# Sheet1.net
KiCad netlist of a schematic drawn in Altium Designer
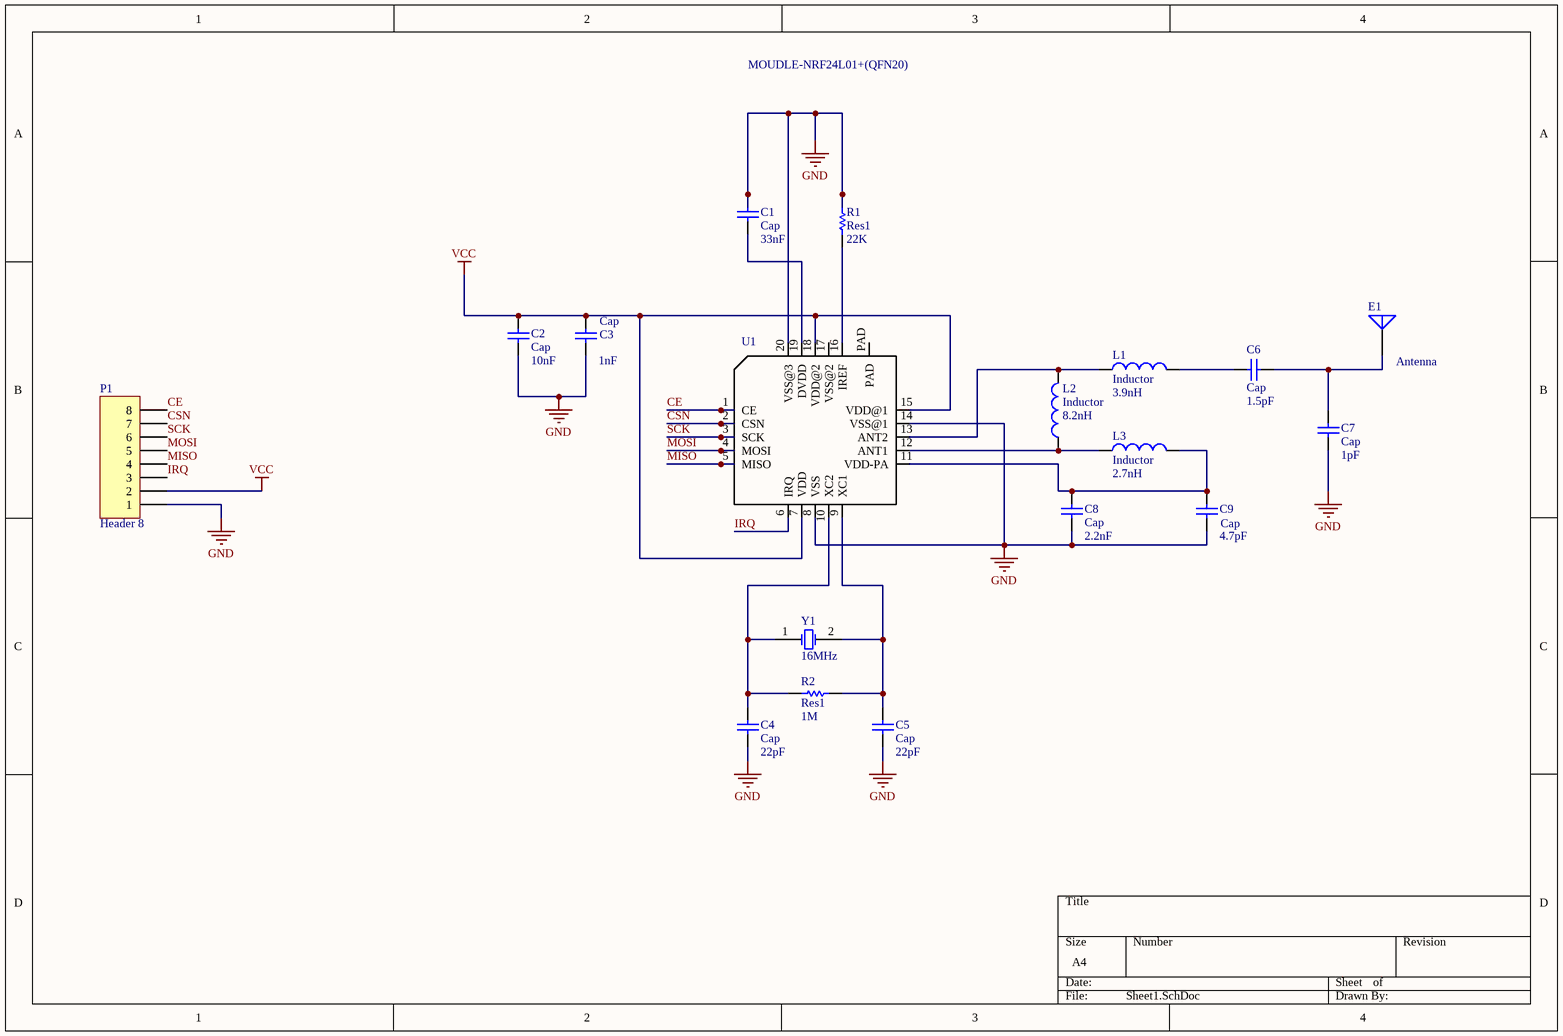
[diagram p0: Sheet1.SchDoc]

(export (version "E")
  (design (tool "Eeschema 10.0.6"))
  (components
    (comp (ref "C1")
      (value "Cap")
      (footprint "6-0805_L")
      (description "Capacitor")
      (fields (field (name "ALTIUM_VALUE") "33nF") (field (name "PUBLISHER") "Altium Limited"))
      (libsource (lib "Miscellaneous Devices") (part "Cap"))
    )
    (comp (ref "C2")
      (value "Cap")
      (footprint "6-0805_L")
      (description "Capacitor")
      (fields (field (name "ALTIUM_VALUE") "10nF") (field (name "PUBLISHER") "Altium Limited"))
      (libsource (lib "Miscellaneous Devices") (part "Cap"))
    )
    (comp (ref "C3")
      (value "Cap")
      (footprint "6-0805_L")
      (description "Capacitor")
      (fields (field (name "ALTIUM_VALUE") "1nF") (field (name "PUBLISHER") "Altium Limited"))
      (libsource (lib "Miscellaneous Devices") (part "Cap"))
    )
    (comp (ref "C4")
      (value "Cap")
      (footprint "6-0805_L")
      (description "Capacitor")
      (fields (field (name "ALTIUM_VALUE") "22pF") (field (name "PUBLISHER") "Altium Limited"))
      (libsource (lib "Miscellaneous Devices") (part "Cap"))
    )
    (comp (ref "C5")
      (value "Cap")
      (footprint "6-0805_L")
      (description "Capacitor")
      (fields (field (name "ALTIUM_VALUE") "22pF") (field (name "PUBLISHER") "Altium Limited"))
      (libsource (lib "Miscellaneous Devices") (part "Cap"))
    )
    (comp (ref "C6")
      (value "Cap")
      (footprint "6-0805_L")
      (description "Capacitor")
      (fields (field (name "ALTIUM_VALUE") "1.5pF") (field (name "PUBLISHER") "Altium Limited"))
      (libsource (lib "Miscellaneous Devices") (part "Cap"))
    )
    (comp (ref "C7")
      (value "Cap")
      (footprint "6-0805_L")
      (description "Capacitor")
      (fields (field (name "ALTIUM_VALUE") "1pF") (field (name "PUBLISHER") "Altium Limited"))
      (libsource (lib "Miscellaneous Devices") (part "Cap"))
    )
    (comp (ref "C8")
      (value "Cap")
      (footprint "6-0805_L")
      (description "Capacitor")
      (fields (field (name "ALTIUM_VALUE") "2.2nF") (field (name "PUBLISHER") "Altium Limited"))
      (libsource (lib "Miscellaneous Devices") (part "Cap"))
    )
    (comp (ref "C9")
      (value "Cap")
      (footprint "6-0805_L")
      (description "Capacitor")
      (fields (field (name "ALTIUM_VALUE") "4.7pF") (field (name "PUBLISHER") "Altium Limited"))
      (libsource (lib "Miscellaneous Devices") (part "Cap"))
    )
    (comp (ref "E1")
      (value "Antenna")
      (footprint "ANT_SMA_RP_FEMEA_90G")
      (description "Generic Antenna")
      (fields (field (name "PUBLISHER") "Altium Limited"))
      (libsource (lib "Miscellaneous Devices") (part "Antenna"))
    )
    (comp (ref "L1")
      (value "Inductor")
      (footprint "0805IND")
      (fields (field (name "ALTIUM_VALUE") "3.9nH") (field (name "PUBLISHER") "Altium Limited"))
      (libsource (lib "Miscellaneous Devices") (part "Inductor"))
    )
    (comp (ref "L2")
      (value "Inductor")
      (footprint "0805IND")
      (fields (field (name "ALTIUM_VALUE") "8.2nH") (field (name "PUBLISHER") "Altium Limited"))
      (libsource (lib "Miscellaneous Devices") (part "Inductor"))
    )
    (comp (ref "L3")
      (value "Inductor")
      (footprint "0805IND")
      (fields (field (name "ALTIUM_VALUE") "2.7nH") (field (name "PUBLISHER") "Altium Limited"))
      (libsource (lib "Miscellaneous Devices") (part "Inductor"))
    )
    (comp (ref "P1")
      (value "Header 8")
      (footprint "HDR2X4")
      (description "Header, 8-Pin")
      (fields (field (name "PUBLISHER") "Altium Limited"))
      (libsource (lib "Miscellaneous Connectors") (part "Header 8"))
    )
    (comp (ref "R1")
      (value "Res1")
      (footprint "6-0805_L")
      (description "Resistor")
      (fields (field (name "ALTIUM_VALUE") "22K") (field (name "PUBLISHER") "Altium Limited"))
      (libsource (lib "Miscellaneous Devices") (part "Res1"))
    )
    (comp (ref "R2")
      (value "Res1")
      (footprint "6-0805_L")
      (description "Resistor")
      (fields (field (name "ALTIUM_VALUE") "1M") (field (name "PUBLISHER") "Altium Limited"))
      (libsource (lib "Miscellaneous Devices") (part "Res1"))
    )
    (comp (ref "U1")
      (value "MOUDLE-NRF24L01+(QFN20)")
      (footprint "*QFN20G-0.5-4X4MM_MOUDLE-NRF24L01+(QFN20)(Primary)")
      (fields (field (name "MP") "NRF24L01+MODULE") (field (name "MF") "Seeed Technology"))
      (libsource (lib "MOUDLE-NRF24L01__QFN20_") (part "MOUDLE-NRF24L01+(QFN20)"))
    )
    (comp (ref "Y1")
      (value "16MHz")
      (footprint "R38")
      (description "Crystal Oscillator")
      (fields (field (name "PUBLISHER") "Altium Limited"))
      (libsource (lib "Miscellaneous Devices") (part "XTAL"))
    )
  )
  (nets
    (net (code "1") (name "/CE") (class "Default")
      (node (ref "P1") (pin "8") (pinfunction "8_8") (pintype "passive"))
      (node (ref "U1") (pin "1") (pinfunction "CE_1") (pintype "bidirectional"))
    )
    (net (code "2") (name "/CSN") (class "Default")
      (node (ref "P1") (pin "7") (pinfunction "7_7") (pintype "passive"))
      (node (ref "U1") (pin "2") (pinfunction "CSN_2") (pintype "bidirectional"))
    )
    (net (code "3") (name "/IRQ") (class "Default")
      (node (ref "P1") (pin "3") (pinfunction "3_3") (pintype "passive"))
      (node (ref "U1") (pin "6") (pinfunction "IRQ_6") (pintype "bidirectional"))
    )
    (net (code "4") (name "/MISO") (class "Default")
      (node (ref "P1") (pin "4") (pinfunction "4_4") (pintype "passive"))
      (node (ref "U1") (pin "5") (pinfunction "MISO_5") (pintype "bidirectional"))
    )
    (net (code "5") (name "/MOSI") (class "Default")
      (node (ref "P1") (pin "5") (pinfunction "5_5") (pintype "passive"))
      (node (ref "U1") (pin "4") (pinfunction "MOSI_4") (pintype "bidirectional"))
    )
    (net (code "6") (name "/SCK") (class "Default")
      (node (ref "P1") (pin "6") (pinfunction "6_6") (pintype "passive"))
      (node (ref "U1") (pin "3") (pinfunction "SCK_3") (pintype "bidirectional"))
    )
    (net (code "7") (name "GND") (class "Default")
      (node (ref "C1") (pin "2") (pinfunction "2_2") (pintype "passive"))
      (node (ref "C2") (pin "1") (pinfunction "1_1") (pintype "passive"))
      (node (ref "C3") (pin "1") (pinfunction "1_1") (pintype "passive"))
      (node (ref "C4") (pin "1") (pinfunction "1_1") (pintype "passive"))
      (node (ref "C5") (pin "1") (pinfunction "1_1") (pintype "passive"))
      (node (ref "C7") (pin "1") (pinfunction "1_1") (pintype "passive"))
      (node (ref "C8") (pin "1") (pinfunction "1_1") (pintype "passive"))
      (node (ref "C9") (pin "1") (pinfunction "1_1") (pintype "passive"))
      (node (ref "P1") (pin "1") (pinfunction "1_1") (pintype "passive"))
      (node (ref "R1") (pin "2") (pinfunction "2_2") (pintype "passive"))
      (node (ref "U1") (pin "14") (pinfunction "VSS@1_14") (pintype "bidirectional"))
      (node (ref "U1") (pin "20") (pinfunction "VSS@3_20") (pintype "bidirectional"))
      (node (ref "U1") (pin "8") (pinfunction "VSS_8") (pintype "bidirectional"))
    )
    (net (code "8") (name "Net-(C6-Pad1)") (class "Default")
      (node (ref "C6") (pin "1") (pinfunction "1_1") (pintype "passive"))
      (node (ref "L1") (pin "2") (pinfunction "2_2") (pintype "passive"))
    )
    (net (code "9") (name "Net-(E1-A)") (class "Default")
      (node (ref "C6") (pin "2") (pinfunction "2_2") (pintype "passive"))
      (node (ref "C7") (pin "2") (pinfunction "2_2") (pintype "passive"))
      (node (ref "E1") (pin "1") (pinfunction "A_1") (pintype "passive"))
    )
    (net (code "10") (name "Net-(U1-ANT1)") (class "Default")
      (node (ref "L2") (pin "1") (pinfunction "1_1") (pintype "passive"))
      (node (ref "L3") (pin "1") (pinfunction "1_1") (pintype "passive"))
      (node (ref "U1") (pin "12") (pinfunction "ANT1_12") (pintype "bidirectional"))
    )
    (net (code "11") (name "Net-(U1-ANT2)") (class "Default")
      (node (ref "L1") (pin "1") (pinfunction "1_1") (pintype "passive"))
      (node (ref "L2") (pin "2") (pinfunction "2_2") (pintype "passive"))
      (node (ref "U1") (pin "13") (pinfunction "ANT2_13") (pintype "bidirectional"))
    )
    (net (code "12") (name "Net-(U1-DVDD)") (class "Default")
      (node (ref "C1") (pin "1") (pinfunction "1_1") (pintype "passive"))
      (node (ref "U1") (pin "19") (pinfunction "DVDD_19") (pintype "bidirectional"))
    )
    (net (code "13") (name "Net-(U1-IREF)") (class "Default")
      (node (ref "R1") (pin "1") (pinfunction "1_1") (pintype "passive"))
      (node (ref "U1") (pin "16") (pinfunction "IREF_16") (pintype "bidirectional"))
    )
    (net (code "14") (name "Net-(U1-VDD-PA)") (class "Default")
      (node (ref "C8") (pin "2") (pinfunction "2_2") (pintype "passive"))
      (node (ref "C9") (pin "2") (pinfunction "2_2") (pintype "passive"))
      (node (ref "L3") (pin "2") (pinfunction "2_2") (pintype "passive"))
      (node (ref "U1") (pin "11") (pinfunction "VDD-PA_11") (pintype "bidirectional"))
    )
    (net (code "15") (name "Net-(U1-XC1)") (class "Default")
      (node (ref "C5") (pin "2") (pinfunction "2_2") (pintype "passive"))
      (node (ref "R2") (pin "2") (pinfunction "2_2") (pintype "passive"))
      (node (ref "U1") (pin "9") (pinfunction "XC1_9") (pintype "bidirectional"))
      (node (ref "Y1") (pin "2") (pinfunction "OSC2_2") (pintype "passive"))
    )
    (net (code "16") (name "Net-(U1-XC2)") (class "Default")
      (node (ref "C4") (pin "2") (pinfunction "2_2") (pintype "passive"))
      (node (ref "R2") (pin "1") (pinfunction "1_1") (pintype "passive"))
      (node (ref "U1") (pin "10") (pinfunction "XC2_10") (pintype "bidirectional"))
      (node (ref "Y1") (pin "1") (pinfunction "OSC1_1") (pintype "passive"))
    )
    (net (code "17") (name "VCC") (class "Default")
      (node (ref "C2") (pin "2") (pinfunction "2_2") (pintype "passive"))
      (node (ref "C3") (pin "2") (pinfunction "2_2") (pintype "passive"))
      (node (ref "P1") (pin "2") (pinfunction "2_2") (pintype "passive"))
      (node (ref "U1") (pin "15") (pinfunction "VDD@1_15") (pintype "bidirectional"))
      (node (ref "U1") (pin "18") (pinfunction "VDD@2_18") (pintype "bidirectional"))
      (node (ref "U1") (pin "7") (pinfunction "VDD_7") (pintype "bidirectional"))
    )
    (net (code "18") (name "unconnected-(U1-PadPAD)") (class "Default")
      (node (ref "U1") (pin "PAD") (pinfunction "PAD_PAD") (pintype "bidirectional"))
    )
    (net (code "19") (name "unconnected-(U1-VSS@2-Pad17)") (class "Default")
      (node (ref "U1") (pin "17") (pinfunction "VSS@2_17") (pintype "bidirectional"))
    )
  )
)
